# Power.net
KiCad netlist of a schematic drawn in Altium Designer
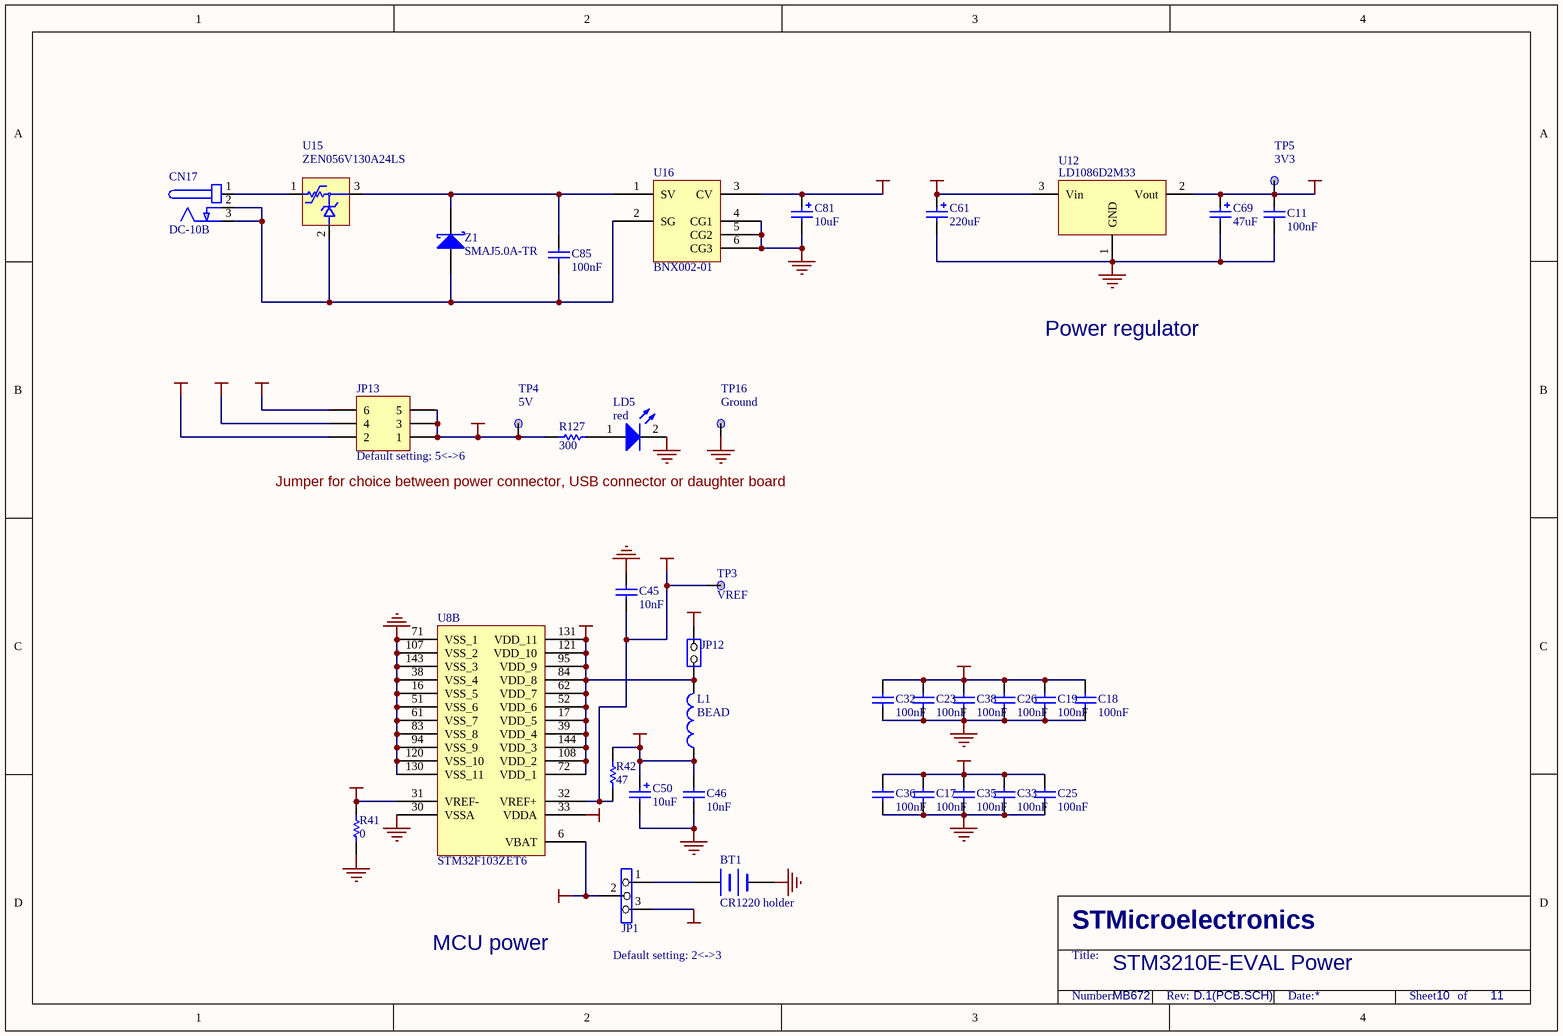
[diagram p0: Power.SchDoc]

(export (version "E")
  (design (tool "Eeschema 10.0.6"))
  (components
    (comp (ref "BT1")
      (value "CR1220 holder")
      (footprint "BATT")
      (description "Battery")
      (libsource (lib "*") (part "BATTERY"))
    )
    (comp (ref "C11")
      (value "100nF")
      (footprint "0603P")
      (description "Capacitor")
      (fields (field (name "PUBLISHER") "Altium Limited"))
      (libsource (lib "Miscellaneous Devices") (part "Cap"))
    )
    (comp (ref "C17")
      (value "100nF")
      (footprint "0603P")
      (description "Capacitor")
      (fields (field (name "PUBLISHER") "Altium Limited"))
      (libsource (lib "Miscellaneous Devices") (part "CAP"))
    )
    (comp (ref "C18")
      (value "100nF")
      (footprint "0603P")
      (description "Capacitor")
      (fields (field (name "PUBLISHER") "Altium Limited"))
      (libsource (lib "Miscellaneous Devices") (part "CAP"))
    )
    (comp (ref "C19")
      (value "100nF")
      (footprint "0603P")
      (description "Capacitor")
      (fields (field (name "PUBLISHER") "Altium Limited"))
      (libsource (lib "Miscellaneous Devices") (part "CAP"))
    )
    (comp (ref "C23")
      (value "100nF")
      (footprint "0603P")
      (description "Capacitor")
      (fields (field (name "PUBLISHER") "Altium Limited"))
      (libsource (lib "Miscellaneous Devices") (part "CAP"))
    )
    (comp (ref "C25")
      (value "100nF")
      (footprint "0603P")
      (description "Capacitor")
      (fields (field (name "PUBLISHER") "Altium Limited"))
      (libsource (lib "Miscellaneous Devices") (part "CAP"))
    )
    (comp (ref "C26")
      (value "100nF")
      (footprint "0603P")
      (description "Capacitor")
      (fields (field (name "PUBLISHER") "Altium Limited"))
      (libsource (lib "Miscellaneous Devices") (part "CAP"))
    )
    (comp (ref "C32")
      (value "100nF")
      (footprint "0603P")
      (description "Capacitor")
      (fields (field (name "PUBLISHER") "Altium Limited"))
      (libsource (lib "Miscellaneous Devices") (part "CAP"))
    )
    (comp (ref "C33")
      (value "100nF")
      (footprint "0603P")
      (description "Capacitor")
      (fields (field (name "PUBLISHER") "Altium Limited"))
      (libsource (lib "Miscellaneous Devices") (part "CAP"))
    )
    (comp (ref "C35")
      (value "100nF")
      (footprint "0603P")
      (description "Capacitor")
      (fields (field (name "PUBLISHER") "Altium Limited"))
      (libsource (lib "Miscellaneous Devices") (part "CAP"))
    )
    (comp (ref "C36")
      (value "100nF")
      (footprint "0603P")
      (description "Capacitor")
      (fields (field (name "PUBLISHER") "Altium Limited"))
      (libsource (lib "Miscellaneous Devices") (part "CAP"))
    )
    (comp (ref "C38")
      (value "100nF")
      (footprint "0603P")
      (description "Capacitor")
      (fields (field (name "PUBLISHER") "Altium Limited"))
      (libsource (lib "Miscellaneous Devices") (part "CAP"))
    )
    (comp (ref "C45")
      (value "10nF")
      (footprint "0603")
      (description "Capacitor")
      (fields (field (name "PUBLISHER") "Altium Limited"))
      (libsource (lib "Miscellaneous Devices") (part "Cap"))
    )
    (comp (ref "C46")
      (value "10nF")
      (footprint "0603")
      (description "Capacitor")
      (fields (field (name "PUBLISHER") "Altium Limited"))
      (libsource (lib "Miscellaneous Devices") (part "Cap"))
    )
    (comp (ref "C50")
      (value "10uF")
      (footprint "TAN-B")
      (description "Polarized Capacitor (Radial)")
      (fields (field (name "PUBLISHER") "Altium Limited"))
      (libsource (lib "Miscellaneous Devices") (part "Cap Pol1"))
    )
    (comp (ref "C61")
      (value "220uF")
      (footprint "C310M")
      (description "Polarized Capacitor (Radial)")
      (fields (field (name "PUBLISHER") "Altium Limited"))
      (libsource (lib "Miscellaneous Devices") (part "Cap Pol1"))
    )
    (comp (ref "C69")
      (value "47uF")
      (footprint "TAN-B")
      (description "Polarized Capacitor (Radial)")
      (fields (field (name "PUBLISHER") "Altium Limited"))
      (libsource (lib "Miscellaneous Devices") (part "Cap Pol1"))
    )
    (comp (ref "C81")
      (value "10uF")
      (footprint "C160M")
      (description "Polarized Capacitor (Radial)")
      (fields (field (name "PUBLISHER") "Altium Limited"))
      (libsource (lib "Miscellaneous Devices") (part "Cap Pol1"))
    )
    (comp (ref "C85")
      (value "100nF")
      (footprint "0603P")
      (description "Capacitor")
      (fields (field (name "PUBLISHER") "Altium Limited"))
      (libsource (lib "Miscellaneous Devices") (part "CAP"))
    )
    (comp (ref "CN17") (value "DC-10B") (footprint "DC10B") (libsource (lib "STR910_SCHLIB") (part "PJ202A")))
    (comp (ref "JP1") (value "~") (footprint "SIP3") (libsource (lib "STR910_SCHLIB") (part "Jumper3")))
    (comp (ref "JP12") (value "~") (footprint "SIP2") (libsource (lib "*") (part "JP2")))
    (comp (ref "JP13")
      (value "~")
      (footprint "2*3P")
      (description "Header, 3-Pin, Dual row")
      (fields (field (name "PUBLISHER") "Altium Limited"))
      (libsource (lib "Miscellaneous Connectors") (part "Header 3X2"))
    )
    (comp (ref "L1")
      (value "BEAD")
      (footprint "0603")
      (description "Inductor")
      (fields (field (name "PUBLISHER") "Altium Limited"))
      (libsource (lib "Miscellaneous Devices") (part "Inductor"))
    )
    (comp (ref "LD5")
      (value "red")
      (footprint "D0603")
      (description "Typical RED, GREEN, YELLOW, AMBER GaAs LED")
      (fields (field (name "PUBLISHER") "Altium Limited"))
      (libsource (lib "Miscellaneous Devices") (part "LED2"))
    )
    (comp (ref "R41")
      (value "0")
      (description "Resistor")
      (fields (field (name "PUBLISHER") "Altium Limited"))
      (libsource (lib "Miscellaneous Devices") (part "Res1"))
    )
    (comp (ref "R42")
      (value "47")
      (description "Resistor")
      (fields (field (name "PUBLISHER") "Altium Limited"))
      (libsource (lib "Miscellaneous Devices") (part "Res1"))
    )
    (comp (ref "R127")
      (value "300")
      (description "Resistor")
      (fields (field (name "PUBLISHER") "Altium Limited"))
      (libsource (lib "Miscellaneous Devices") (part "res1"))
    )
    (comp (ref "TP3") (value "VREF") (footprint "TP") (libsource (lib "*") (part "TP")))
    (comp (ref "TP4") (value "5V") (footprint "TP") (libsource (lib "*") (part "TP")))
    (comp (ref "TP5") (value "3V3") (footprint "TP") (libsource (lib "*") (part "TP")))
    (comp (ref "TP16") (value "Ground") (footprint "TP") (libsource (lib "*") (part "TP")))
    (comp (ref "U8") (value "STM32F103ZET6") (libsource (lib "MB672") (part "BigPiranha_new")))
    (comp (ref "U12") (value "LD1086D2M33") (footprint "D2PAK/A") (libsource (lib "*") (part "VOLTREG1")))
    (comp (ref "U15")
      (value "ZEN056V130A24LS")
      (footprint "polyzen")
      (libsource (lib "STR910_SCHLIB") (part "ZEN056V130A24LS"))
    )
    (comp (ref "U16")
      (value "BNX002-01")
      (footprint "BNX001")
      (libsource (lib "STR910_SCHLIB") (part "BNX002"))
    )
    (comp (ref "Z1")
      (value "SMAJ5.0A-TR")
      (footprint "1R1C")
      (description "Schottky Diode")
      (fields (field (name "PUBLISHER") "Altium Limited"))
      (libsource (lib "Miscellaneous Devices") (part "D Schottky"))
    )
  )
  (nets
    (net (code "1") (name "+3V3") (class "Default")
      (node (ref "C11") (pin "1") (pinfunction "1_1") (pintype "passive"))
      (node (ref "C69") (pin "1") (pinfunction "1_1") (pintype "passive"))
      (node (ref "JP1") (pin "3") (pintype "passive"))
      (node (ref "JP12") (pin "2") (pinfunction "NO_2") (pintype "passive"))
      (node (ref "TP5") (pin "1") (pinfunction "1_1") (pintype "passive"))
      (node (ref "U12") (pin "2") (pinfunction "Vout_2") (pintype "passive"))
    )
    (net (code "2") (name "+5V") (class "Default")
      (node (ref "C61") (pin "1") (pinfunction "1_1") (pintype "passive"))
      (node (ref "JP13") (pin "1") (pinfunction "1_1") (pintype "passive"))
      (node (ref "JP13") (pin "3") (pinfunction "3_3") (pintype "passive"))
      (node (ref "JP13") (pin "5") (pinfunction "5_5") (pintype "passive"))
      (node (ref "R127") (pin "2") (pinfunction "2_2") (pintype "passive"))
      (node (ref "TP4") (pin "1") (pinfunction "1_1") (pintype "passive"))
      (node (ref "U12") (pin "3") (pinfunction "Vin_3") (pintype "passive"))
    )
    (net (code "3") (name "D5V") (class "Default")
      (node (ref "JP13") (pin "4") (pinfunction "4_4") (pintype "passive"))
    )
    (net (code "4") (name "E5V") (class "Default")
      (node (ref "C81") (pin "1") (pinfunction "1_1") (pintype "passive"))
      (node (ref "JP13") (pin "6") (pinfunction "6_6") (pintype "passive"))
      (node (ref "U16") (pin "3") (pinfunction "CV_3") (pintype "passive"))
    )
    (net (code "5") (name "GND") (class "Default")
      (node (ref "BT1") (pin "2") (pinfunction "-_2") (pintype "passive"))
      (node (ref "C11") (pin "2") (pinfunction "2_2") (pintype "passive"))
      (node (ref "C17") (pin "2") (pinfunction "2_2") (pintype "passive"))
      (node (ref "C18") (pin "2") (pinfunction "2_2") (pintype "passive"))
      (node (ref "C19") (pin "2") (pinfunction "2_2") (pintype "passive"))
      (node (ref "C23") (pin "2") (pinfunction "2_2") (pintype "passive"))
      (node (ref "C25") (pin "2") (pinfunction "2_2") (pintype "passive"))
      (node (ref "C26") (pin "2") (pinfunction "2_2") (pintype "passive"))
      (node (ref "C32") (pin "2") (pinfunction "2_2") (pintype "passive"))
      (node (ref "C33") (pin "2") (pinfunction "2_2") (pintype "passive"))
      (node (ref "C35") (pin "2") (pinfunction "2_2") (pintype "passive"))
      (node (ref "C36") (pin "2") (pinfunction "2_2") (pintype "passive"))
      (node (ref "C38") (pin "2") (pinfunction "2_2") (pintype "passive"))
      (node (ref "C45") (pin "2") (pinfunction "2_2") (pintype "passive"))
      (node (ref "C46") (pin "1") (pinfunction "1_1") (pintype "passive"))
      (node (ref "C50") (pin "2") (pinfunction "2_2") (pintype "passive"))
      (node (ref "C61") (pin "2") (pinfunction "2_2") (pintype "passive"))
      (node (ref "C69") (pin "2") (pinfunction "2_2") (pintype "passive"))
      (node (ref "C81") (pin "2") (pinfunction "2_2") (pintype "passive"))
      (node (ref "LD5") (pin "2") (pinfunction "K_2") (pintype "passive"))
      (node (ref "R41") (pin "2") (pinfunction "2_2") (pintype "passive"))
      (node (ref "TP16") (pin "1") (pinfunction "1_1") (pintype "passive"))
      (node (ref "U12") (pin "1") (pinfunction "GND_1") (pintype "passive"))
      (node (ref "U16") (pin "4") (pinfunction "CG1_4") (pintype "passive"))
      (node (ref "U16") (pin "5") (pinfunction "CG2_5") (pintype "passive"))
      (node (ref "U16") (pin "6") (pinfunction "CG3_6") (pintype "passive"))
      (node (ref "U8") (pin "107") (pinfunction "VSS_2_107") (pintype "passive"))
      (node (ref "U8") (pin "120") (pinfunction "VSS_10_120") (pintype "passive"))
      (node (ref "U8") (pin "130") (pinfunction "VSS_11_130") (pintype "passive"))
      (node (ref "U8") (pin "143") (pinfunction "VSS_3_143") (pintype "passive"))
      (node (ref "U8") (pin "16") (pinfunction "VSS_5_16") (pintype "passive"))
      (node (ref "U8") (pin "30") (pinfunction "VSSA_30") (pintype "passive"))
      (node (ref "U8") (pin "38") (pinfunction "VSS_4_38") (pintype "passive"))
      (node (ref "U8") (pin "51") (pinfunction "VSS_6_51") (pintype "passive"))
      (node (ref "U8") (pin "61") (pinfunction "VSS_7_61") (pintype "passive"))
      (node (ref "U8") (pin "71") (pinfunction "VSS_1_71") (pintype "passive"))
      (node (ref "U8") (pin "83") (pinfunction "VSS_8_83") (pintype "passive"))
      (node (ref "U8") (pin "94") (pinfunction "VSS_9_94") (pintype "passive"))
    )
    (net (code "6") (name "Net-(BT1-+)") (class "Default")
      (node (ref "BT1") (pin "1") (pinfunction "+_1") (pintype "passive"))
      (node (ref "JP1") (pin "1") (pintype "passive"))
    )
    (net (code "7") (name "Net-(CN17-+)") (class "Default")
      (node (ref "CN17") (pin "1") (pinfunction "+_1") (pintype "passive"))
      (node (ref "U15") (pin "1") (pintype "passive"))
    )
    (net (code "8") (name "Net-(LD5-A)") (class "Default")
      (node (ref "LD5") (pin "1") (pinfunction "A_1") (pintype "passive"))
      (node (ref "R127") (pin "1") (pinfunction "1_1") (pintype "passive"))
    )
    (net (code "9") (name "Net-(U16-SG)") (class "Default")
      (node (ref "C85") (pin "2") (pinfunction "2_2") (pintype "passive"))
      (node (ref "CN17") (pin "2") (pinfunction "GND_2") (pintype "passive"))
      (node (ref "CN17") (pin "3") (pinfunction "GND_3") (pintype "passive"))
      (node (ref "U15") (pin "2") (pintype "passive"))
      (node (ref "U16") (pin "2") (pinfunction "SG_2") (pintype "passive"))
      (node (ref "Z1") (pin "1") (pinfunction "A_1") (pintype "passive"))
    )
    (net (code "10") (name "Net-(U16-SV)") (class "Default")
      (node (ref "C85") (pin "1") (pinfunction "1_1") (pintype "passive"))
      (node (ref "U15") (pin "3") (pintype "passive"))
      (node (ref "U16") (pin "1") (pinfunction "SV_1") (pintype "passive"))
      (node (ref "Z1") (pin "2") (pinfunction "K_2") (pintype "passive"))
    )
    (net (code "11") (name "U5V") (class "Default")
      (node (ref "JP13") (pin "2") (pinfunction "2_2") (pintype "passive"))
    )
    (net (code "12") (name "VDD") (class "Default")
      (node (ref "C17") (pin "1") (pinfunction "1_1") (pintype "passive"))
      (node (ref "C18") (pin "1") (pinfunction "1_1") (pintype "passive"))
      (node (ref "C19") (pin "1") (pinfunction "1_1") (pintype "passive"))
      (node (ref "C23") (pin "1") (pinfunction "1_1") (pintype "passive"))
      (node (ref "C25") (pin "1") (pinfunction "1_1") (pintype "passive"))
      (node (ref "C26") (pin "1") (pinfunction "1_1") (pintype "passive"))
      (node (ref "C32") (pin "1") (pinfunction "1_1") (pintype "passive"))
      (node (ref "C33") (pin "1") (pinfunction "1_1") (pintype "passive"))
      (node (ref "C35") (pin "1") (pinfunction "1_1") (pintype "passive"))
      (node (ref "C36") (pin "1") (pinfunction "1_1") (pintype "passive"))
      (node (ref "C38") (pin "1") (pinfunction "1_1") (pintype "passive"))
      (node (ref "JP12") (pin "1") (pinfunction "COMMON_1") (pintype "passive"))
      (node (ref "L1") (pin "2") (pinfunction "2_2") (pintype "passive"))
      (node (ref "U8") (pin "108") (pinfunction "VDD_2_108") (pintype "passive"))
      (node (ref "U8") (pin "121") (pinfunction "VDD_10_121") (pintype "passive"))
      (node (ref "U8") (pin "131") (pinfunction "VDD_11_131") (pintype "passive"))
      (node (ref "U8") (pin "144") (pinfunction "VDD_3_144") (pintype "passive"))
      (node (ref "U8") (pin "17") (pinfunction "VDD_5_17") (pintype "passive"))
      (node (ref "U8") (pin "39") (pinfunction "VDD_4_39") (pintype "passive"))
      (node (ref "U8") (pin "52") (pinfunction "VDD_6_52") (pintype "passive"))
      (node (ref "U8") (pin "62") (pinfunction "VDD_7_62") (pintype "passive"))
      (node (ref "U8") (pin "72") (pinfunction "VDD_1_72") (pintype "passive"))
      (node (ref "U8") (pin "84") (pinfunction "VDD_8_84") (pintype "passive"))
      (node (ref "U8") (pin "95") (pinfunction "VDD_9_95") (pintype "passive"))
    )
    (net (code "13") (name "VDDA") (class "Default")
      (node (ref "C46") (pin "2") (pinfunction "2_2") (pintype "passive"))
      (node (ref "C50") (pin "1") (pinfunction "1_1") (pintype "passive"))
      (node (ref "L1") (pin "1") (pinfunction "1_1") (pintype "passive"))
      (node (ref "R42") (pin "2") (pinfunction "2_2") (pintype "passive"))
      (node (ref "U8") (pin "33") (pinfunction "VDDA_33") (pintype "passive"))
    )
    (net (code "14") (name "VREF+") (class "Default")
      (node (ref "C45") (pin "1") (pinfunction "1_1") (pintype "passive"))
      (node (ref "R42") (pin "1") (pinfunction "1_1") (pintype "passive"))
      (node (ref "TP3") (pin "1") (pinfunction "1_1") (pintype "passive"))
      (node (ref "U8") (pin "32") (pinfunction "VREF+_32") (pintype "passive"))
    )
    (net (code "15") (name "VREF-") (class "Default")
      (node (ref "R41") (pin "1") (pinfunction "1_1") (pintype "passive"))
      (node (ref "U8") (pin "31") (pinfunction "VREF-_31") (pintype "passive"))
    )
    (net (code "16") (name "Vbat") (class "Default")
      (node (ref "JP1") (pin "2") (pintype "passive"))
      (node (ref "U8") (pin "6") (pinfunction "VBAT_6") (pintype "passive"))
    )
  )
)
